# design.net
KiCad netlist of a schematic drawn in Altium Designer
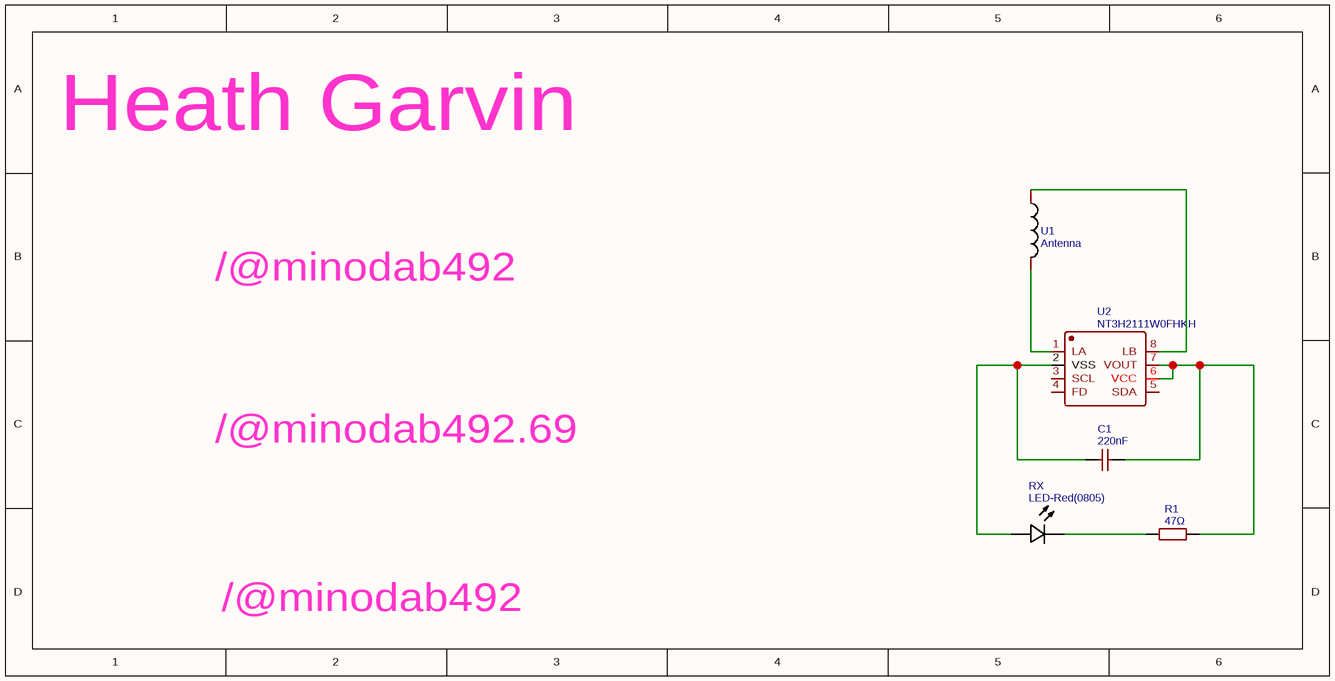
[diagram p0: design.schdoc]

(export (version "E")
  (design (tool "Eeschema 10.0.6"))
  (components
    (comp (ref "C1")
      (value "220nF")
      (fields
        (field (name "MANUFACTURER PART") "CL10B224KA8NNNC")
        (field (name "MANUFACTURER") "SAMSUNG(三星)")
      )
      (libsource (lib "altium-import") (part "root_0_220nF_"))
    )
    (comp (ref "R1")
      (value "47Ω")
      (fields
        (field (name "MANUFACTURER") "UNI-ROYAL(厚声)")
        (field (name "MANUFACTURER PART") "0603WAF470JT5E")
      )
      (libsource (lib "altium-import") (part "root_0_47Ω_"))
    )
    (comp (ref "RX")
      (value "LED-Red(0805)")
      (fields
        (field (name "MANUFACTURER") "Hubei KENTO Elec")
        (field (name "MANUFACTURER PART") "17-21SUYC/TR8")
        (field (name "CONTRIBUTOR") "pavol.machala")
      )
      (libsource (lib "altium-import") (part "root_0_LED-Red(0805)_"))
    )
    (comp (ref "U1")
      (value "Antenna")
      (fields (field (name "CONTRIBUTOR") "maggie.j.liu"))
      (libsource (lib "altium-import") (part "root_0_Antenna_"))
    )
    (comp (ref "U2")
      (value "NT3H2111W0FHKH")
      (fields (field (name "MANUFACTURER") "NXP(恩智浦)") (field (name "CONTRIBUTOR") "LCSC"))
      (libsource (lib "altium-import") (part "root_0_NT3H2111W0FHKH_"))
    )
  )
  (nets
    (net (code "1") (name "Net-(RX-+)") (class "Default")
      (node (ref "C1") (pin "1") (pinfunction "1_1") (pintype "passive"))
      (node (ref "RX") (pin "1") (pinfunction "+_1") (pintype "passive"))
      (node (ref "U2") (pin "2") (pinfunction "VSS_2") (pintype "passive"))
    )
    (net (code "2") (name "Net-(RX--)") (class "Default")
      (node (ref "R1") (pin "1") (pinfunction "1_1") (pintype "passive"))
      (node (ref "RX") (pin "2") (pinfunction "-_2") (pintype "passive"))
    )
    (net (code "3") (name "Net-(U2-LA)") (class "Default")
      (node (ref "U1") (pin "P$1") (pinfunction "P$1_P$1") (pintype "passive"))
      (node (ref "U2") (pin "1") (pinfunction "LA_1") (pintype "passive"))
    )
    (net (code "4") (name "Net-(U2-LB)") (class "Default")
      (node (ref "U1") (pin "P$2") (pinfunction "P$2_P$2") (pintype "passive"))
      (node (ref "U2") (pin "8") (pinfunction "LB_8") (pintype "passive"))
    )
    (net (code "5") (name "Net-(U2-VCC)") (class "Default")
      (node (ref "C1") (pin "2") (pinfunction "2_2") (pintype "passive"))
      (node (ref "R1") (pin "2") (pinfunction "2_2") (pintype "passive"))
      (node (ref "U2") (pin "6") (pinfunction "VCC_6") (pintype "passive"))
      (node (ref "U2") (pin "7") (pinfunction "VOUT_7") (pintype "passive"))
    )
    (net (code "6") (name "unconnected-(U2-FD-Pad4)") (class "Default")
      (node (ref "U2") (pin "4") (pinfunction "FD_4") (pintype "passive"))
    )
    (net (code "7") (name "unconnected-(U2-SCL-Pad3)") (class "Default")
      (node (ref "U2") (pin "3") (pinfunction "SCL_3") (pintype "passive"))
    )
    (net (code "8") (name "unconnected-(U2-SDA-Pad5)") (class "Default")
      (node (ref "U2") (pin "5") (pinfunction "SDA_5") (pintype "passive"))
    )
  )
)
